# Adafruit_PiTFT_2_8inch_Resistive_PCB.net
KiCad netlist of a schematic drawn in EAGLE
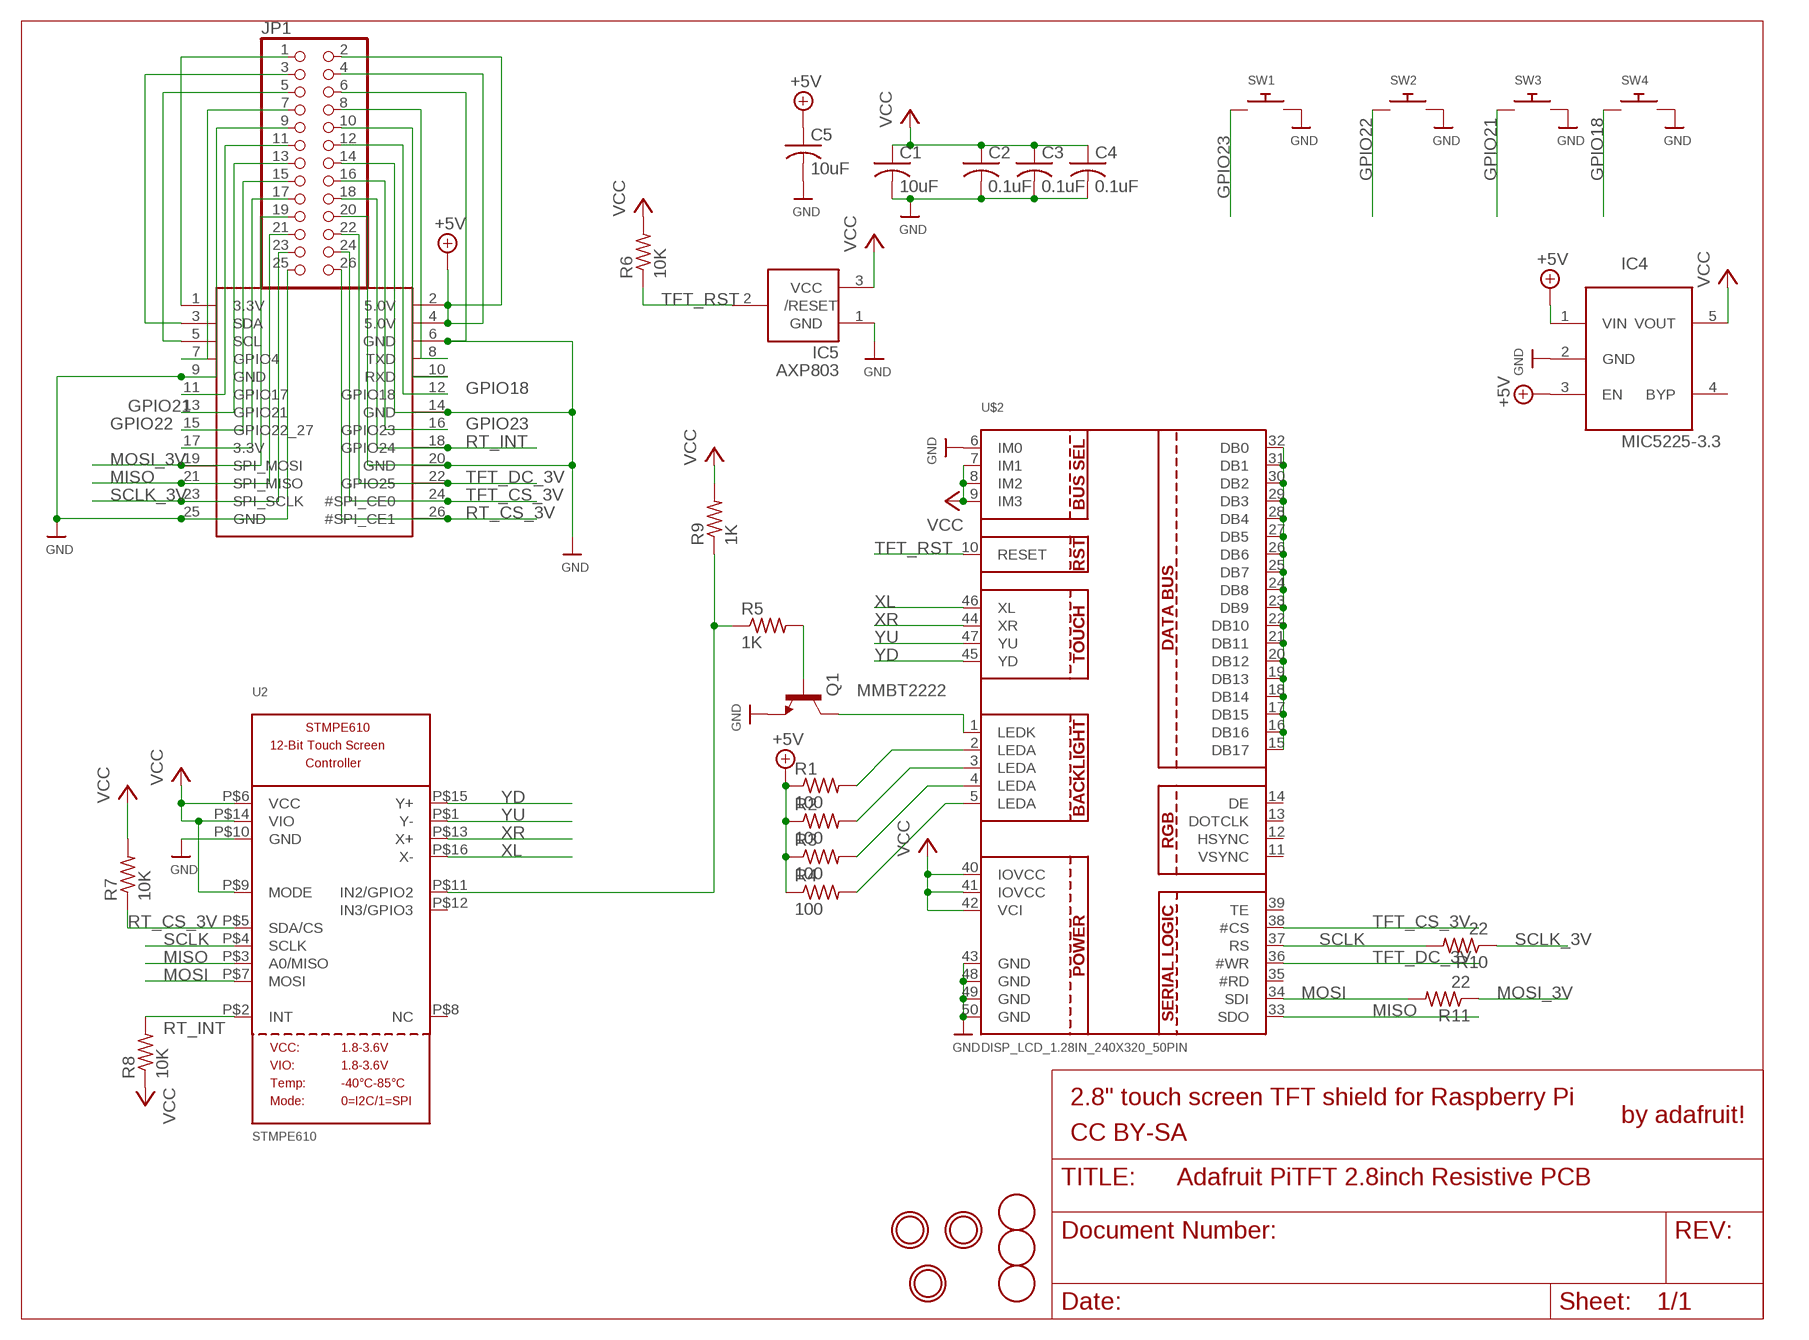
[diagram p0: schematic, sheet 1]

(export (version "E")
  (design (tool "Eeschema 10.0.6"))
  (components
    (comp (ref "C1")
      (value "10uF")
      (footprint "eagle-import:C0805K")
      (libsource (lib "eagle-import") (part "C-USC0805K"))
    )
    (comp (ref "C2")
      (value "0.1uF")
      (footprint "eagle-import:C0805K")
      (libsource (lib "eagle-import") (part "C-USC0805K"))
    )
    (comp (ref "C3")
      (value "0.1uF")
      (footprint "eagle-import:C0805K")
      (libsource (lib "eagle-import") (part "C-USC0805K"))
    )
    (comp (ref "C4")
      (value "0.1uF")
      (footprint "eagle-import:C0805K")
      (libsource (lib "eagle-import") (part "C-USC0805K"))
    )
    (comp (ref "C5")
      (value "10uF")
      (footprint "eagle-import:C0805K")
      (libsource (lib "eagle-import") (part "C-USC0805K"))
    )
    (comp (ref "IC4")
      (value "MIC5225-3.3")
      (footprint "eagle-import:SOT23-5L")
      (libsource (lib "eagle-import") (part "LP298XS"))
    )
    (comp (ref "IC5")
      (value "AXP803")
      (footprint "eagle-import:SOT23")
      (libsource (lib "eagle-import") (part "AXP083-SAG"))
    )
    (comp (ref "JP1")
      (value "HEADER-2X13")
      (footprint "eagle-import:2X13")
      (libsource (lib "eagle-import") (part "HEADER-2X13"))
    )
    (comp (ref "Q1")
      (value "MMBT2222")
      (footprint "eagle-import:SOT23-BEC")
      (libsource (lib "eagle-import") (part "-NPN-SOT23-BECMMBT2222ALT1"))
    )
    (comp (ref "R1")
      (value "100")
      (footprint "eagle-import:R0805")
      (libsource (lib "eagle-import") (part "R-US_R0805"))
    )
    (comp (ref "R2")
      (value "100")
      (footprint "eagle-import:R0805")
      (libsource (lib "eagle-import") (part "R-US_R0805"))
    )
    (comp (ref "R3")
      (value "100")
      (footprint "eagle-import:R0805")
      (libsource (lib "eagle-import") (part "R-US_R0805"))
    )
    (comp (ref "R4")
      (value "100")
      (footprint "eagle-import:R0805")
      (libsource (lib "eagle-import") (part "R-US_R0805"))
    )
    (comp (ref "R5")
      (value "1K")
      (footprint "eagle-import:R0805")
      (libsource (lib "eagle-import") (part "R-US_R0805"))
    )
    (comp (ref "R6")
      (value "10K")
      (footprint "eagle-import:R0805")
      (libsource (lib "eagle-import") (part "R-US_R0805"))
    )
    (comp (ref "R7")
      (value "10K")
      (footprint "eagle-import:R0805")
      (libsource (lib "eagle-import") (part "R-US_R0805"))
    )
    (comp (ref "R8")
      (value "10K")
      (footprint "eagle-import:R0805")
      (libsource (lib "eagle-import") (part "R-US_R0805"))
    )
    (comp (ref "R9")
      (value "1K")
      (footprint "eagle-import:R0805")
      (libsource (lib "eagle-import") (part "R-US_R0805"))
    )
    (comp (ref "R10")
      (value "22")
      (footprint "eagle-import:R0805")
      (libsource (lib "eagle-import") (part "R-US_R0805"))
    )
    (comp (ref "R11")
      (value "22")
      (footprint "eagle-import:R0805")
      (libsource (lib "eagle-import") (part "R-US_R0805"))
    )
    (comp (ref "SW1")
      (value "SWITCH_PUSHBUTTONEVQ-PE")
      (footprint "eagle-import:TACT_PANA-EVQ")
      (libsource (lib "eagle-import") (part "SWITCH_PUSHBUTTONEVQ-PE"))
    )
    (comp (ref "SW2")
      (value "SWITCH_PUSHBUTTONEVQ-PE")
      (footprint "eagle-import:TACT_PANA-EVQ")
      (libsource (lib "eagle-import") (part "SWITCH_PUSHBUTTONEVQ-PE"))
    )
    (comp (ref "SW3")
      (value "SWITCH_PUSHBUTTONEVQ-PE")
      (footprint "eagle-import:TACT_PANA-EVQ")
      (libsource (lib "eagle-import") (part "SWITCH_PUSHBUTTONEVQ-PE"))
    )
    (comp (ref "SW4")
      (value "SWITCH_PUSHBUTTONEVQ-PE")
      (footprint "eagle-import:TACT_PANA-EVQ")
      (libsource (lib "eagle-import") (part "SWITCH_PUSHBUTTONEVQ-PE"))
    )
    (comp (ref "U$2")
      (value "DISP_LCD_1.28IN_240X320_50PIN")
      (footprint "eagle-import:TFT_2.83IN_240X320_50PIN")
      (libsource (lib "eagle-import") (part "DISP_LCD_1.28IN_240X320_50PIN"))
    )
    (comp (ref "U$3")
      (value "RASPBERRYPI_B_MODELB_V2")
      (footprint "eagle-import:RASPBERRYPIV2_SHIELD")
      (libsource (lib "eagle-import") (part "RASPBERRYPI_B_MODELB_V2"))
    )
    (comp (ref "U$10")
      (value "FIDUCIAL")
      (footprint "eagle-import:FIDUCIAL_1MM")
      (libsource (lib "eagle-import") (part "FIDUCIAL"))
    )
    (comp (ref "U$11")
      (value "FIDUCIAL")
      (footprint "eagle-import:FIDUCIAL_1MM")
      (libsource (lib "eagle-import") (part "FIDUCIAL"))
    )
    (comp (ref "U$15")
      (value "MOUNTINGHOLE2.5_THICK")
      (footprint "eagle-import:MOUNTINGHOLE_2.5_PLATED_THICK")
      (libsource (lib "eagle-import") (part "MOUNTINGHOLE2.5_THICK"))
    )
    (comp (ref "U$16")
      (value "MOUNTINGHOLE2.5_THICK")
      (footprint "eagle-import:MOUNTINGHOLE_2.5_PLATED_THICK")
      (libsource (lib "eagle-import") (part "MOUNTINGHOLE2.5_THICK"))
    )
    (comp (ref "U$17")
      (value "MOUNTINGHOLE2.5_THICK")
      (footprint "eagle-import:MOUNTINGHOLE_2.5_PLATED_THICK")
      (fields (field (name "BOM") "EXCLUDE"))
      (libsource (lib "eagle-import") (part "MOUNTINGHOLE2.5_THICK"))
    )
    (comp (ref "U$18")
      (value "FIDUCIAL")
      (footprint "eagle-import:FIDUCIAL_1MM")
      (libsource (lib "eagle-import") (part "FIDUCIAL"))
    )
    (comp (ref "U2")
      (value "STMPE610")
      (footprint "eagle-import:QFN16_3MM")
      (libsource (lib "eagle-import") (part "STMPE610"))
    )
  )
  (nets
    (net (code "1") (name "+5V") (class "Default")
      (node (ref "C5") (pin "1") (pinfunction "1_1") (pintype "passive"))
      (node (ref "IC4") (pin "1") (pinfunction "VIN_1") (pintype "bidirectional"))
      (node (ref "IC4") (pin "3") (pinfunction "EN_3") (pintype "bidirectional"))
      (node (ref "JP1") (pin "2") (pinfunction "2_2") (pintype "passive"))
      (node (ref "JP1") (pin "4") (pinfunction "4_4") (pintype "passive"))
      (node (ref "R1") (pin "1") (pinfunction "1_1") (pintype "passive"))
      (node (ref "R2") (pin "1") (pinfunction "1_1") (pintype "passive"))
      (node (ref "R3") (pin "1") (pinfunction "1_1") (pintype "passive"))
      (node (ref "R4") (pin "1") (pinfunction "1_1") (pintype "passive"))
      (node (ref "U$3") (pin "2") (pinfunction "5.0V_2") (pintype "power_in"))
      (node (ref "U$3") (pin "4") (pinfunction "5.0V_4") (pintype "power_in"))
    )
    (net (code "2") (name "/GPIO18") (class "Default")
      (node (ref "JP1") (pin "12") (pinfunction "12_12") (pintype "passive"))
      (node (ref "SW4") (pin "P$1") (pinfunction "P$1_P$1") (pintype "passive"))
      (node (ref "U$3") (pin "12") (pinfunction "GPIO18_12") (pintype "bidirectional"))
    )
    (net (code "3") (name "/GPIO21") (class "Default")
      (node (ref "JP1") (pin "13") (pinfunction "13_13") (pintype "passive"))
      (node (ref "SW3") (pin "P$1") (pinfunction "P$1_P$1") (pintype "passive"))
      (node (ref "U$3") (pin "13") (pinfunction "GPIO21_13") (pintype "bidirectional"))
    )
    (net (code "4") (name "/GPIO22") (class "Default")
      (node (ref "JP1") (pin "15") (pinfunction "15_15") (pintype "passive"))
      (node (ref "SW2") (pin "P$1") (pinfunction "P$1_P$1") (pintype "passive"))
      (node (ref "U$3") (pin "15") (pinfunction "GPIO22_27_15") (pintype "bidirectional"))
    )
    (net (code "5") (name "/GPIO23") (class "Default")
      (node (ref "JP1") (pin "16") (pinfunction "16_16") (pintype "passive"))
      (node (ref "SW1") (pin "P$1") (pinfunction "P$1_P$1") (pintype "passive"))
      (node (ref "U$3") (pin "16") (pinfunction "GPIO23_16") (pintype "bidirectional"))
    )
    (net (code "6") (name "/MISO") (class "Default")
      (node (ref "JP1") (pin "21") (pinfunction "21_21") (pintype "passive"))
      (node (ref "U$2") (pin "33") (pinfunction "SDO_33") (pintype "bidirectional"))
      (node (ref "U$3") (pin "21") (pinfunction "SPI_MISO_21") (pintype "input"))
      (node (ref "U2") (pin "P$3") (pinfunction "A0/MISO_P$3") (pintype "bidirectional"))
    )
    (net (code "7") (name "/MOSI") (class "Default")
      (node (ref "R11") (pin "2") (pinfunction "2_2") (pintype "passive"))
      (node (ref "U$2") (pin "34") (pinfunction "SDI_34") (pintype "bidirectional"))
      (node (ref "U2") (pin "P$7") (pinfunction "MOSI_P$7") (pintype "input"))
    )
    (net (code "8") (name "/MOSI_3V") (class "Default")
      (node (ref "JP1") (pin "19") (pinfunction "19_19") (pintype "passive"))
      (node (ref "R11") (pin "1") (pinfunction "1_1") (pintype "passive"))
      (node (ref "U$3") (pin "19") (pinfunction "SPI_MOSI_19") (pintype "bidirectional"))
    )
    (net (code "9") (name "/RT_CS_3V") (class "Default")
      (node (ref "JP1") (pin "26") (pinfunction "26_26") (pintype "passive"))
      (node (ref "R7") (pin "1") (pinfunction "1_1") (pintype "passive"))
      (node (ref "U$3") (pin "26") (pinfunction "#SPI_CE1_26") (pintype "bidirectional"))
      (node (ref "U2") (pin "P$5") (pinfunction "SDA/CS_P$5") (pintype "bidirectional"))
    )
    (net (code "10") (name "/RT_INT") (class "Default")
      (node (ref "JP1") (pin "18") (pinfunction "18_18") (pintype "passive"))
      (node (ref "R8") (pin "2") (pinfunction "2_2") (pintype "passive"))
      (node (ref "U$3") (pin "18") (pinfunction "GPIO24_18") (pintype "bidirectional"))
      (node (ref "U2") (pin "P$2") (pinfunction "INT_P$2") (pintype "output"))
    )
    (net (code "11") (name "/SCLK") (class "Default")
      (node (ref "R10") (pin "2") (pinfunction "2_2") (pintype "passive"))
      (node (ref "U$2") (pin "37") (pinfunction "RS_37") (pintype "bidirectional"))
      (node (ref "U2") (pin "P$4") (pinfunction "SCLK_P$4") (pintype "bidirectional"))
    )
    (net (code "12") (name "/SCLK_3V") (class "Default")
      (node (ref "JP1") (pin "23") (pinfunction "23_23") (pintype "passive"))
      (node (ref "R10") (pin "1") (pinfunction "1_1") (pintype "passive"))
      (node (ref "U$3") (pin "23") (pinfunction "SPI_SCLK_23") (pintype "bidirectional"))
    )
    (net (code "13") (name "/TFT_CS_3V") (class "Default")
      (node (ref "JP1") (pin "24") (pinfunction "24_24") (pintype "passive"))
      (node (ref "U$2") (pin "38") (pinfunction "#CS_38") (pintype "bidirectional"))
      (node (ref "U$3") (pin "24") (pinfunction "#SPI_CE0_24") (pintype "bidirectional"))
    )
    (net (code "14") (name "/TFT_DC_3V") (class "Default")
      (node (ref "JP1") (pin "22") (pinfunction "22_22") (pintype "passive"))
      (node (ref "U$2") (pin "36") (pinfunction "#WR_36") (pintype "bidirectional"))
      (node (ref "U$3") (pin "22") (pinfunction "GPIO25_22") (pintype "bidirectional"))
    )
    (net (code "15") (name "/TFT_RST") (class "Default")
      (node (ref "IC5") (pin "2") (pinfunction "/RESET_2") (pintype "output"))
      (node (ref "R6") (pin "1") (pinfunction "1_1") (pintype "passive"))
      (node (ref "U$2") (pin "10") (pinfunction "RESET_10") (pintype "bidirectional"))
    )
    (net (code "16") (name "/XL") (class "Default")
      (node (ref "U$2") (pin "46") (pinfunction "XL_46") (pintype "bidirectional"))
      (node (ref "U2") (pin "P$16") (pinfunction "X-_P$16") (pintype "input"))
    )
    (net (code "17") (name "/XR") (class "Default")
      (node (ref "U$2") (pin "44") (pinfunction "XR_44") (pintype "bidirectional"))
      (node (ref "U2") (pin "P$13") (pinfunction "X+_P$13") (pintype "input"))
    )
    (net (code "18") (name "/YD") (class "Default")
      (node (ref "U$2") (pin "45") (pinfunction "YD_45") (pintype "bidirectional"))
      (node (ref "U2") (pin "P$15") (pinfunction "Y+_P$15") (pintype "input"))
    )
    (net (code "19") (name "/YU") (class "Default")
      (node (ref "U$2") (pin "47") (pinfunction "YU_47") (pintype "bidirectional"))
      (node (ref "U2") (pin "P$1") (pinfunction "Y-_P$1") (pintype "input"))
    )
    (net (code "20") (name "GND") (class "Default")
      (node (ref "C1") (pin "2") (pinfunction "2_2") (pintype "passive"))
      (node (ref "C2") (pin "2") (pinfunction "2_2") (pintype "passive"))
      (node (ref "C3") (pin "2") (pinfunction "2_2") (pintype "passive"))
      (node (ref "C4") (pin "2") (pinfunction "2_2") (pintype "passive"))
      (node (ref "C5") (pin "2") (pinfunction "2_2") (pintype "passive"))
      (node (ref "IC4") (pin "2") (pinfunction "GND_2") (pintype "bidirectional"))
      (node (ref "IC5") (pin "1") (pinfunction "GND_1") (pintype "power_in"))
      (node (ref "JP1") (pin "14") (pinfunction "14_14") (pintype "passive"))
      (node (ref "JP1") (pin "20") (pinfunction "20_20") (pintype "passive"))
      (node (ref "JP1") (pin "25") (pinfunction "25_25") (pintype "passive"))
      (node (ref "JP1") (pin "6") (pinfunction "6_6") (pintype "passive"))
      (node (ref "JP1") (pin "9") (pinfunction "9_9") (pintype "passive"))
      (node (ref "Q1") (pin "E") (pinfunction "E_E") (pintype "passive"))
      (node (ref "SW1") (pin "P$2") (pinfunction "P$2_P$2") (pintype "passive"))
      (node (ref "SW2") (pin "P$2") (pinfunction "P$2_P$2") (pintype "passive"))
      (node (ref "SW3") (pin "P$2") (pinfunction "P$2_P$2") (pintype "passive"))
      (node (ref "SW4") (pin "P$2") (pinfunction "P$2_P$2") (pintype "passive"))
      (node (ref "U$2") (pin "43") (pinfunction "GND_43") (pintype "bidirectional"))
      (node (ref "U$2") (pin "48") (pinfunction "GND_48") (pintype "bidirectional"))
      (node (ref "U$2") (pin "49") (pinfunction "GND_49") (pintype "bidirectional"))
      (node (ref "U$2") (pin "50") (pinfunction "GND_50") (pintype "bidirectional"))
      (node (ref "U$2") (pin "6") (pinfunction "IM0_6") (pintype "bidirectional"))
      (node (ref "U$3") (pin "14") (pinfunction "GND_14") (pintype "power_in"))
      (node (ref "U$3") (pin "20") (pinfunction "GND_20") (pintype "power_in"))
      (node (ref "U$3") (pin "25") (pinfunction "GND_25") (pintype "power_in"))
      (node (ref "U$3") (pin "6") (pinfunction "GND_6") (pintype "power_in"))
      (node (ref "U$3") (pin "9") (pinfunction "GND_9") (pintype "power_in"))
      (node (ref "U2") (pin "P$10") (pinfunction "GND_P$10") (pintype "power_in"))
    )
    (net (code "21") (name "Net-(JP1-Pad1)") (class "Default")
      (node (ref "JP1") (pin "1") (pinfunction "1_1") (pintype "passive"))
      (node (ref "U$3") (pin "1") (pinfunction "3.3V_1") (pintype "power_in"))
    )
    (net (code "22") (name "Net-(JP1-Pad17)") (class "Default")
      (node (ref "JP1") (pin "17") (pinfunction "17_17") (pintype "passive"))
      (node (ref "U$3") (pin "17") (pinfunction "3.3V_17") (pintype "power_in"))
    )
    (net (code "23") (name "Net-(Q1-PadB)") (class "Default")
      (node (ref "Q1") (pin "B") (pinfunction "B_B") (pintype "passive"))
      (node (ref "R5") (pin "2") (pinfunction "2_2") (pintype "passive"))
    )
    (net (code "24") (name "Net-(R1-Pad2)") (class "Default")
      (node (ref "R1") (pin "2") (pinfunction "2_2") (pintype "passive"))
      (node (ref "U$2") (pin "2") (pinfunction "LEDA_2") (pintype "bidirectional"))
    )
    (net (code "25") (name "Net-(R2-Pad2)") (class "Default")
      (node (ref "R2") (pin "2") (pinfunction "2_2") (pintype "passive"))
      (node (ref "U$2") (pin "3") (pinfunction "LEDA_3") (pintype "bidirectional"))
    )
    (net (code "26") (name "Net-(R3-Pad2)") (class "Default")
      (node (ref "R3") (pin "2") (pinfunction "2_2") (pintype "passive"))
      (node (ref "U$2") (pin "4") (pinfunction "LEDA_4") (pintype "bidirectional"))
    )
    (net (code "27") (name "Net-(R4-Pad2)") (class "Default")
      (node (ref "R4") (pin "2") (pinfunction "2_2") (pintype "passive"))
      (node (ref "U$2") (pin "5") (pinfunction "LEDA_5") (pintype "bidirectional"))
    )
    (net (code "28") (name "Net-(U$2-DB0)") (class "Default")
      (node (ref "U$2") (pin "15") (pinfunction "DB17_15") (pintype "bidirectional"))
      (node (ref "U$2") (pin "16") (pinfunction "DB16_16") (pintype "bidirectional"))
      (node (ref "U$2") (pin "17") (pinfunction "DB15_17") (pintype "bidirectional"))
      (node (ref "U$2") (pin "18") (pinfunction "DB14_18") (pintype "bidirectional"))
      (node (ref "U$2") (pin "19") (pinfunction "DB13_19") (pintype "bidirectional"))
      (node (ref "U$2") (pin "20") (pinfunction "DB12_20") (pintype "bidirectional"))
      (node (ref "U$2") (pin "21") (pinfunction "DB11_21") (pintype "bidirectional"))
      (node (ref "U$2") (pin "22") (pinfunction "DB10_22") (pintype "bidirectional"))
      (node (ref "U$2") (pin "23") (pinfunction "DB9_23") (pintype "bidirectional"))
      (node (ref "U$2") (pin "24") (pinfunction "DB8_24") (pintype "bidirectional"))
      (node (ref "U$2") (pin "25") (pinfunction "DB7_25") (pintype "bidirectional"))
      (node (ref "U$2") (pin "26") (pinfunction "DB6_26") (pintype "bidirectional"))
      (node (ref "U$2") (pin "27") (pinfunction "DB5_27") (pintype "bidirectional"))
      (node (ref "U$2") (pin "28") (pinfunction "DB4_28") (pintype "bidirectional"))
      (node (ref "U$2") (pin "29") (pinfunction "DB3_29") (pintype "bidirectional"))
      (node (ref "U$2") (pin "30") (pinfunction "DB2_30") (pintype "bidirectional"))
      (node (ref "U$2") (pin "31") (pinfunction "DB1_31") (pintype "bidirectional"))
      (node (ref "U$2") (pin "32") (pinfunction "DB0_32") (pintype "bidirectional"))
    )
    (net (code "29") (name "Net-(U$2-LEDK)") (class "Default")
      (node (ref "Q1") (pin "C") (pinfunction "C_C") (pintype "passive"))
      (node (ref "U$2") (pin "1") (pinfunction "LEDK_1") (pintype "bidirectional"))
    )
    (net (code "30") (name "Net-(U$3-GPIO4)") (class "Default")
      (node (ref "JP1") (pin "7") (pinfunction "7_7") (pintype "passive"))
      (node (ref "U$3") (pin "7") (pinfunction "GPIO4_7") (pintype "bidirectional"))
    )
    (net (code "31") (name "Net-(U$3-GPIO17)") (class "Default")
      (node (ref "JP1") (pin "11") (pinfunction "11_11") (pintype "passive"))
      (node (ref "U$3") (pin "11") (pinfunction "GPIO17_11") (pintype "bidirectional"))
    )
    (net (code "32") (name "Net-(U$3-RXD)") (class "Default")
      (node (ref "JP1") (pin "10") (pinfunction "10_10") (pintype "passive"))
      (node (ref "U$3") (pin "10") (pinfunction "RXD_10") (pintype "input"))
    )
    (net (code "33") (name "Net-(U$3-SCL)") (class "Default")
      (node (ref "JP1") (pin "5") (pinfunction "5_5") (pintype "passive"))
      (node (ref "U$3") (pin "5") (pinfunction "SCL_5") (pintype "bidirectional"))
    )
    (net (code "34") (name "Net-(U$3-SDA)") (class "Default")
      (node (ref "JP1") (pin "3") (pinfunction "3_3") (pintype "passive"))
      (node (ref "U$3") (pin "3") (pinfunction "SDA_3") (pintype "bidirectional"))
    )
    (net (code "35") (name "Net-(U$3-TXD)") (class "Default")
      (node (ref "JP1") (pin "8") (pinfunction "8_8") (pintype "passive"))
      (node (ref "U$3") (pin "8") (pinfunction "TXD_8") (pintype "output"))
    )
    (net (code "36") (name "Net-(U2-IN2{slash}GPIO2)") (class "Default")
      (node (ref "R5") (pin "1") (pinfunction "1_1") (pintype "passive"))
      (node (ref "R9") (pin "1") (pinfunction "1_1") (pintype "passive"))
      (node (ref "U2") (pin "P$11") (pinfunction "IN2/GPIO2_P$11") (pintype "bidirectional"))
    )
    (net (code "37") (name "VCC") (class "Default")
      (node (ref "C1") (pin "1") (pinfunction "1_1") (pintype "passive"))
      (node (ref "C2") (pin "1") (pinfunction "1_1") (pintype "passive"))
      (node (ref "C3") (pin "1") (pinfunction "1_1") (pintype "passive"))
      (node (ref "C4") (pin "1") (pinfunction "1_1") (pintype "passive"))
      (node (ref "IC4") (pin "5") (pinfunction "VOUT_5") (pintype "bidirectional"))
      (node (ref "IC5") (pin "3") (pinfunction "VCC_3") (pintype "power_in"))
      (node (ref "R6") (pin "2") (pinfunction "2_2") (pintype "passive"))
      (node (ref "R7") (pin "2") (pinfunction "2_2") (pintype "passive"))
      (node (ref "R8") (pin "1") (pinfunction "1_1") (pintype "passive"))
      (node (ref "R9") (pin "2") (pinfunction "2_2") (pintype "passive"))
      (node (ref "U$2") (pin "40") (pinfunction "IOVCC_40") (pintype "bidirectional"))
      (node (ref "U$2") (pin "41") (pinfunction "IOVCC_41") (pintype "bidirectional"))
      (node (ref "U$2") (pin "42") (pinfunction "VCI_42") (pintype "bidirectional"))
      (node (ref "U$2") (pin "7") (pinfunction "IM1_7") (pintype "bidirectional"))
      (node (ref "U$2") (pin "8") (pinfunction "IM2_8") (pintype "bidirectional"))
      (node (ref "U$2") (pin "9") (pinfunction "IM3_9") (pintype "bidirectional"))
      (node (ref "U2") (pin "P$14") (pinfunction "VIO_P$14") (pintype "power_in"))
      (node (ref "U2") (pin "P$6") (pinfunction "VCC_P$6") (pintype "power_in"))
      (node (ref "U2") (pin "P$9") (pinfunction "MODE_P$9") (pintype "input"))
    )
    (net (code "38") (name "unconnected-(IC4-BYP-Pad4)") (class "Default")
      (node (ref "IC4") (pin "4") (pinfunction "BYP_4") (pintype "bidirectional"))
    )
    (net (code "39") (name "unconnected-(U$2-#RD-Pad35)") (class "Default")
      (node (ref "U$2") (pin "35") (pinfunction "#RD_35") (pintype "bidirectional"))
    )
    (net (code "40") (name "unconnected-(U$2-DE-Pad14)") (class "Default")
      (node (ref "U$2") (pin "14") (pinfunction "DE_14") (pintype "bidirectional"))
    )
    (net (code "41") (name "unconnected-(U$2-DOTCLK-Pad13)") (class "Default")
      (node (ref "U$2") (pin "13") (pinfunction "DOTCLK_13") (pintype "bidirectional"))
    )
    (net (code "42") (name "unconnected-(U$2-HSYNC-Pad12)") (class "Default")
      (node (ref "U$2") (pin "12") (pinfunction "HSYNC_12") (pintype "bidirectional"))
    )
    (net (code "43") (name "unconnected-(U$2-TE-Pad39)") (class "Default")
      (node (ref "U$2") (pin "39") (pinfunction "TE_39") (pintype "bidirectional"))
    )
    (net (code "44") (name "unconnected-(U$2-VSYNC-Pad11)") (class "Default")
      (node (ref "U$2") (pin "11") (pinfunction "VSYNC_11") (pintype "bidirectional"))
    )
    (net (code "45") (name "unconnected-(U2-IN3{slash}GPIO3-PadP$12)") (class "Default")
      (node (ref "U2") (pin "P$12") (pinfunction "IN3/GPIO3_P$12") (pintype "bidirectional"))
    )
    (net (code "46") (name "unconnected-(U2-NC-PadP$8)") (class "Default")
      (node (ref "U2") (pin "P$8") (pinfunction "NC_P$8") (pintype "no_connect"))
    )
  )
)
